# display.net
KiCad netlist of a schematic drawn in Altium Designer
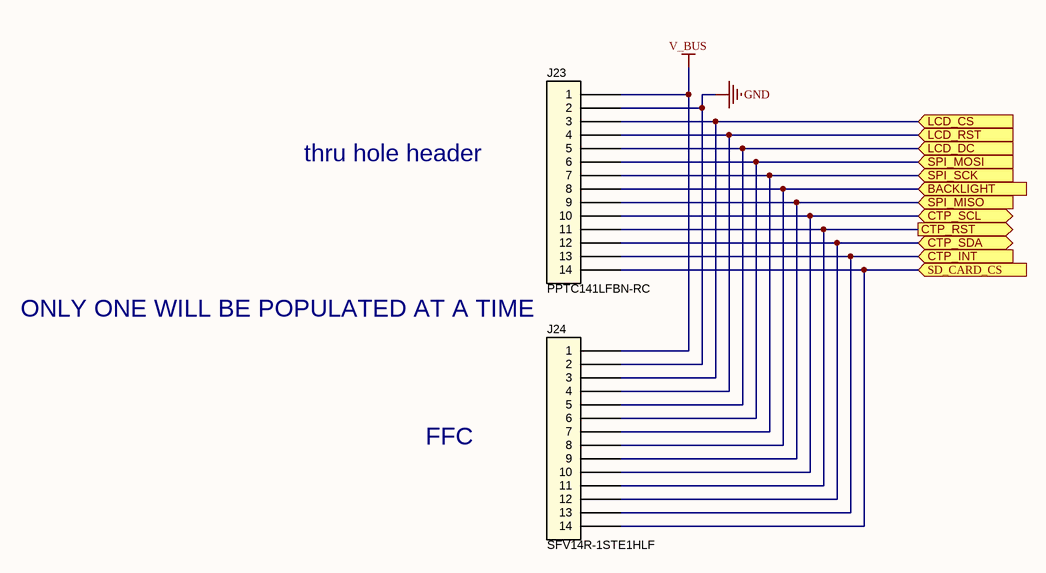
[diagram p0: display.SchDoc]

(export (version "E")
  (design (tool "Eeschema 10.0.6"))
  (components
    (comp (ref "J23")
      (value "PPTC141LFBN-RC")
      (footprint "CONN_SULLINS_PPTC141LFBN-RC")
      (description "CONN HEADER RECEPTACLE VERT 14POS 2.54MM GOLD")
      (fields (field (name "MFR") "Sullins Connector Solutions"))
      (libsource (lib "General_Library") (part "CMP-007-0083"))
    )
    (comp (ref "J24")
      (value "SFV14R-1STE1HLF")
      (footprint "CONN_AMPHENOL_SFV14R-1STE1HLF")
      (description "CONN FFC BOTTOM 14POS 0.5MM R/A")
      (fields (field (name "MFR") "Amphenol ICC (FCI)"))
      (libsource (lib "General_Library") (part "CMP-007-0082"))
    )
  )
  (nets
    (net (code "1") (name "/BACKLIGHT") (class "Default")
      (node (ref "J23") (pin "8") (pinfunction "8_8") (pintype "passive"))
      (node (ref "J24") (pin "8") (pinfunction "8_8") (pintype "passive"))
    )
    (net (code "2") (name "/CTP_INT") (class "Default")
      (node (ref "J23") (pin "13") (pinfunction "13_13") (pintype "passive"))
      (node (ref "J24") (pin "13") (pinfunction "13_13") (pintype "passive"))
    )
    (net (code "3") (name "/CTP_RST") (class "Default")
      (node (ref "J23") (pin "11") (pinfunction "11_11") (pintype "passive"))
      (node (ref "J24") (pin "11") (pinfunction "11_11") (pintype "passive"))
    )
    (net (code "4") (name "/CTP_SCL") (class "Default")
      (node (ref "J23") (pin "10") (pinfunction "10_10") (pintype "passive"))
      (node (ref "J24") (pin "10") (pinfunction "10_10") (pintype "passive"))
    )
    (net (code "5") (name "/CTP_SDA") (class "Default")
      (node (ref "J23") (pin "12") (pinfunction "12_12") (pintype "passive"))
      (node (ref "J24") (pin "12") (pinfunction "12_12") (pintype "passive"))
    )
    (net (code "6") (name "/LCD_CS") (class "Default")
      (node (ref "J23") (pin "3") (pinfunction "3_3") (pintype "passive"))
      (node (ref "J24") (pin "3") (pinfunction "3_3") (pintype "passive"))
    )
    (net (code "7") (name "/LCD_DC") (class "Default")
      (node (ref "J23") (pin "5") (pinfunction "5_5") (pintype "passive"))
      (node (ref "J24") (pin "5") (pinfunction "5_5") (pintype "passive"))
    )
    (net (code "8") (name "/LCD_RST") (class "Default")
      (node (ref "J23") (pin "4") (pinfunction "4_4") (pintype "passive"))
      (node (ref "J24") (pin "4") (pinfunction "4_4") (pintype "passive"))
    )
    (net (code "9") (name "/SD_CARD_CS") (class "Default")
      (node (ref "J23") (pin "14") (pinfunction "14_14") (pintype "passive"))
      (node (ref "J24") (pin "14") (pinfunction "14_14") (pintype "passive"))
    )
    (net (code "10") (name "/SPI_MISO") (class "Default")
      (node (ref "J23") (pin "9") (pinfunction "9_9") (pintype "passive"))
      (node (ref "J24") (pin "9") (pinfunction "9_9") (pintype "passive"))
    )
    (net (code "11") (name "/SPI_MOSI") (class "Default")
      (node (ref "J23") (pin "6") (pinfunction "6_6") (pintype "passive"))
      (node (ref "J24") (pin "6") (pinfunction "6_6") (pintype "passive"))
    )
    (net (code "12") (name "/SPI_SCK") (class "Default")
      (node (ref "J23") (pin "7") (pinfunction "7_7") (pintype "passive"))
      (node (ref "J24") (pin "7") (pinfunction "7_7") (pintype "passive"))
    )
    (net (code "13") (name "GND") (class "Default")
      (node (ref "J23") (pin "2") (pinfunction "2_2") (pintype "passive"))
      (node (ref "J24") (pin "2") (pinfunction "2_2") (pintype "passive"))
    )
    (net (code "14") (name "V_BUS") (class "Default")
      (node (ref "J23") (pin "1") (pinfunction "1_1") (pintype "passive"))
      (node (ref "J24") (pin "1") (pinfunction "1_1") (pintype "passive"))
    )
  )
)
